# play.net
KiCad netlist of a schematic drawn in EAGLE
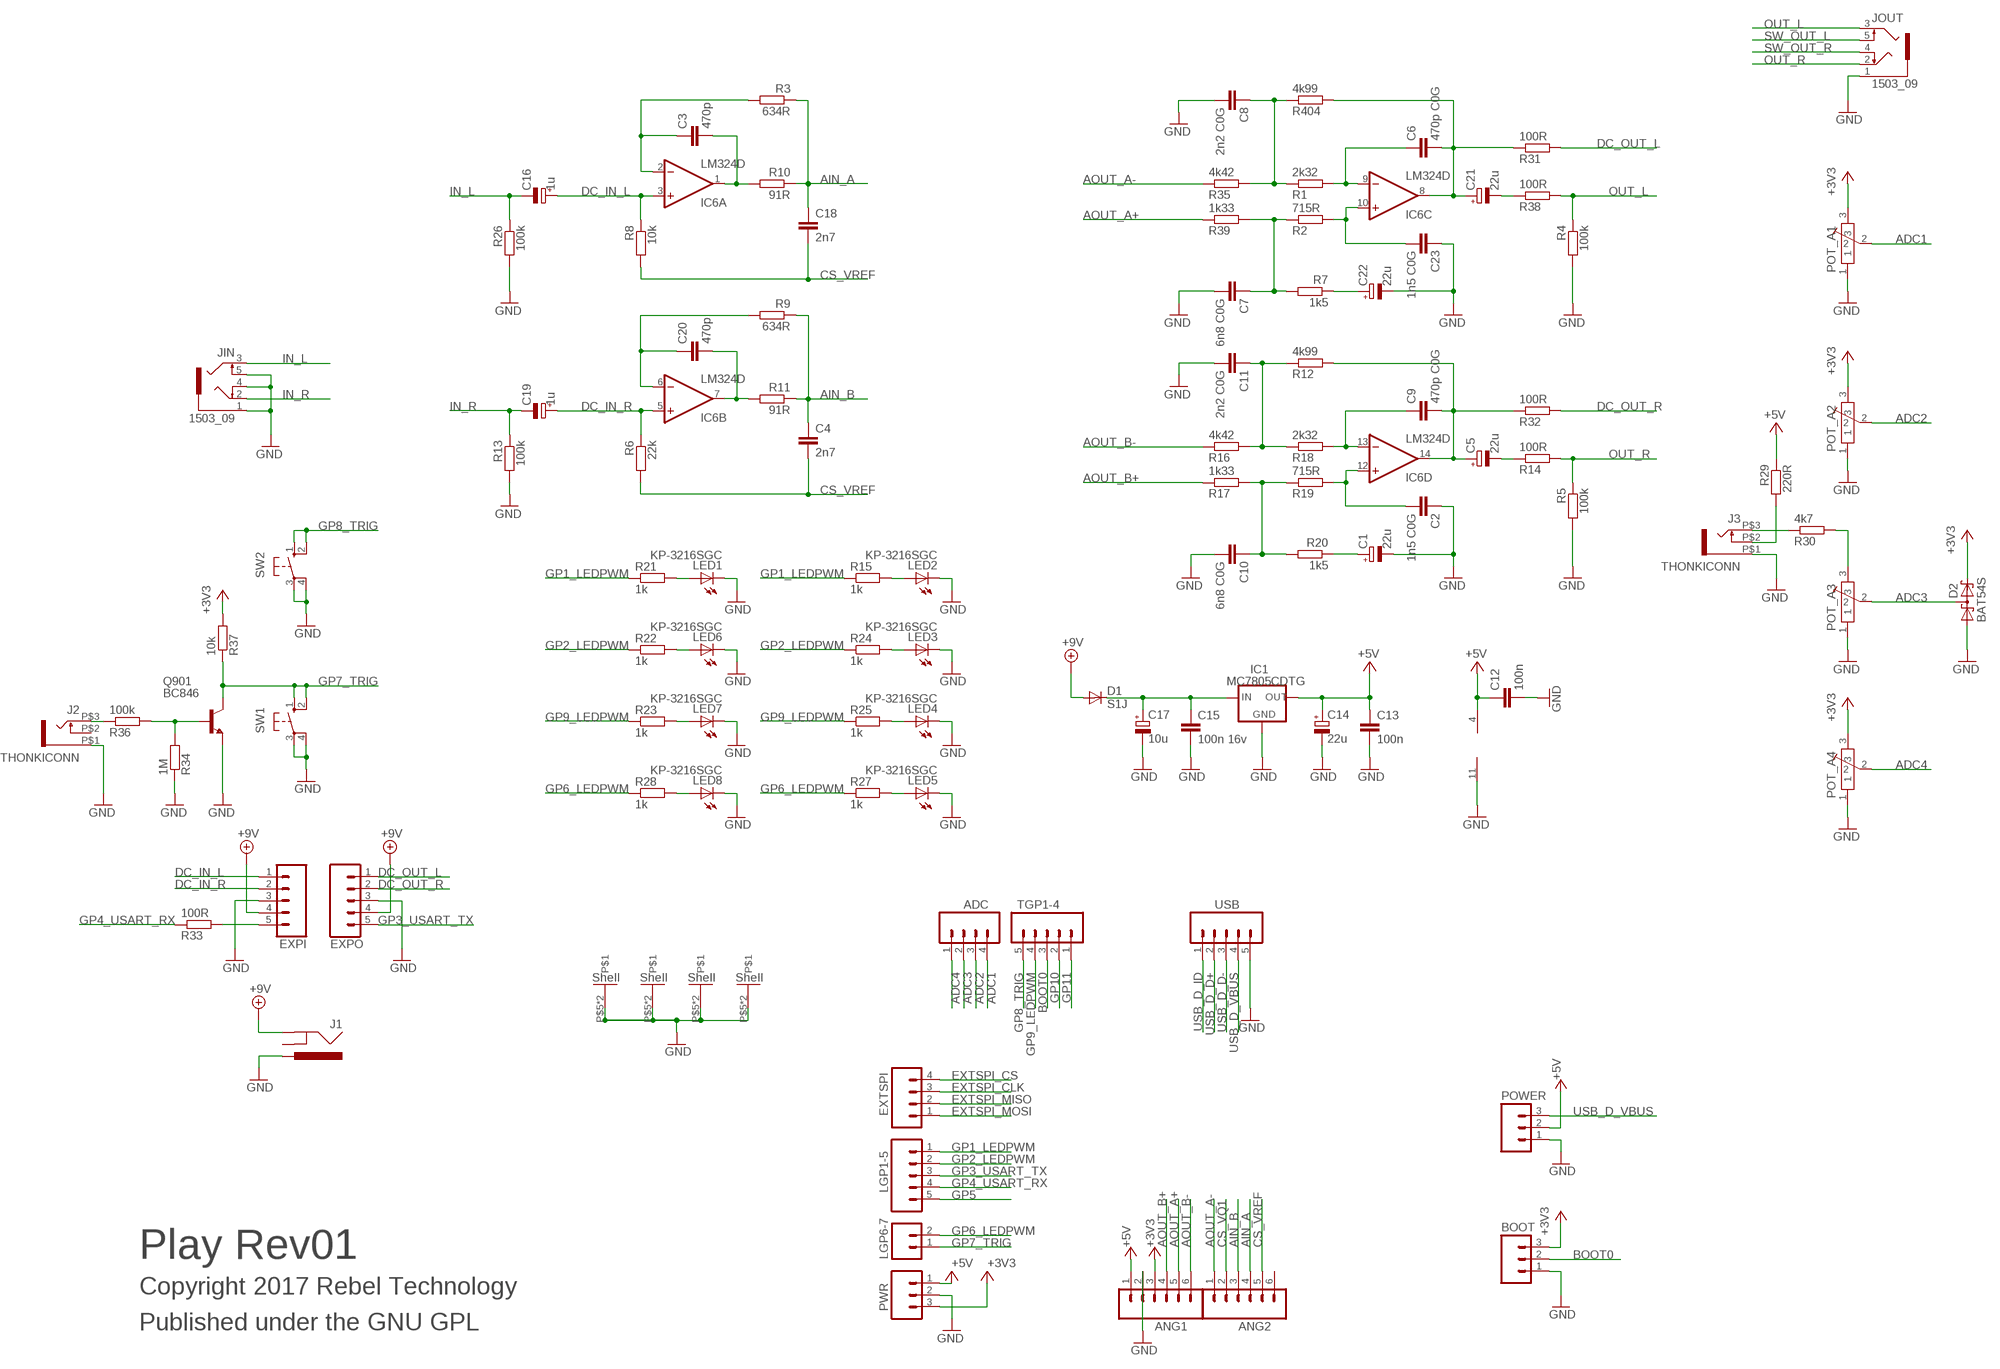
[diagram p0: schematic, sheet 1]

(export (version "E")
  (design (tool "Eeschema 10.0.6"))
  (components
    (comp (ref "ADC")
      (value "M04PTH")
      (footprint "eagle-import:1X04")
      (libsource (lib "eagle-import") (part "M04PTH"))
    )
    (comp (ref "ANG1")
      (value "M06SIP")
      (footprint "eagle-import:1X06")
      (libsource (lib "eagle-import") (part "M06SIP"))
    )
    (comp (ref "ANG2")
      (value "M06SIP")
      (footprint "eagle-import:1X06")
      (libsource (lib "eagle-import") (part "M06SIP"))
    )
    (comp (ref "BOOT")
      (value "M03PTH")
      (footprint "eagle-import:1X03")
      (libsource (lib "eagle-import") (part "M03PTH"))
    )
    (comp (ref "C1")
      (value "22u")
      (footprint "eagle-import:CPOL-5")
      (libsource (lib "eagle-import") (part "CPOL-EU153CLV-0505"))
    )
    (comp (ref "C2")
      (value "1n5 C0G")
      (footprint "eagle-import:C0603")
      (libsource (lib "eagle-import") (part "resistor_C-EUC0603"))
    )
    (comp (ref "C3")
      (value "470p")
      (footprint "eagle-import:C0603")
      (libsource (lib "eagle-import") (part "resistor_C-EUC0603"))
    )
    (comp (ref "C4")
      (value "2n7")
      (footprint "eagle-import:C0603")
      (libsource (lib "eagle-import") (part "resistor_C-EUC0603"))
    )
    (comp (ref "C5")
      (value "22u")
      (footprint "eagle-import:CPOL-5")
      (libsource (lib "eagle-import") (part "CPOL-EU153CLV-0505"))
    )
    (comp (ref "C6")
      (value "470p C0G")
      (footprint "eagle-import:C0603")
      (libsource (lib "eagle-import") (part "resistor_C-EUC0603"))
    )
    (comp (ref "C7")
      (value "6n8 C0G")
      (footprint "eagle-import:C0603")
      (libsource (lib "eagle-import") (part "resistor_C-EUC0603"))
    )
    (comp (ref "C8")
      (value "2n2 C0G")
      (footprint "eagle-import:C0603")
      (libsource (lib "eagle-import") (part "resistor_C-EUC0603"))
    )
    (comp (ref "C9")
      (value "470p C0G")
      (footprint "eagle-import:C0603")
      (libsource (lib "eagle-import") (part "resistor_C-EUC0603"))
    )
    (comp (ref "C10")
      (value "6n8 C0G")
      (footprint "eagle-import:C0603")
      (libsource (lib "eagle-import") (part "resistor_C-EUC0603"))
    )
    (comp (ref "C11")
      (value "2n2 C0G")
      (footprint "eagle-import:C0603")
      (libsource (lib "eagle-import") (part "resistor_C-EUC0603"))
    )
    (comp (ref "C12")
      (value "100n")
      (footprint "eagle-import:C0603")
      (libsource (lib "eagle-import") (part "resistor_C-EUC0603"))
    )
    (comp (ref "C13")
      (value "100n")
      (footprint "eagle-import:C0603")
      (libsource (lib "eagle-import") (part "C-EUC0603"))
    )
    (comp (ref "C14")
      (value "22u")
      (footprint "eagle-import:CPOL-5")
      (libsource (lib "eagle-import") (part "CPOL-EU153CLV-0505"))
    )
    (comp (ref "C15")
      (value "100n 16v")
      (footprint "eagle-import:C0603")
      (libsource (lib "eagle-import") (part "C-EUC0603"))
    )
    (comp (ref "C16")
      (value "1u")
      (footprint "eagle-import:153CLV-0405")
      (libsource (lib "eagle-import") (part "CPOL-EU153CLV-0405"))
    )
    (comp (ref "C17")
      (value "10u")
      (footprint "eagle-import:153CLV-0405")
      (libsource (lib "eagle-import") (part "CPOL-EU153CLV-0405"))
    )
    (comp (ref "C18")
      (value "2n7")
      (footprint "eagle-import:C0603")
      (libsource (lib "eagle-import") (part "resistor_C-EUC0603"))
    )
    (comp (ref "C19")
      (value "1u")
      (footprint "eagle-import:153CLV-0405")
      (libsource (lib "eagle-import") (part "CPOL-EU153CLV-0405"))
    )
    (comp (ref "C20")
      (value "470p")
      (footprint "eagle-import:C0603")
      (libsource (lib "eagle-import") (part "resistor_C-EUC0603"))
    )
    (comp (ref "C21")
      (value "22u")
      (footprint "eagle-import:CPOL-5")
      (libsource (lib "eagle-import") (part "CPOL-EU153CLV-0505"))
    )
    (comp (ref "C22")
      (value "22u")
      (footprint "eagle-import:CPOL-5")
      (libsource (lib "eagle-import") (part "CPOL-EU153CLV-0505"))
    )
    (comp (ref "C23")
      (value "1n5 C0G")
      (footprint "eagle-import:C0603")
      (libsource (lib "eagle-import") (part "resistor_C-EUC0603"))
    )
    (comp (ref "D1")
      (value "S1J")
      (footprint "eagle-import:SMA-DIODE")
      (libsource (lib "eagle-import") (part "DIODESMA"))
    )
    (comp (ref "D2")
      (value "BAT54S")
      (footprint "eagle-import:SOT23")
      (libsource (lib "eagle-import") (part "BAT54S"))
    )
    (comp (ref "EXPI")
      (value "M05PTH")
      (footprint "eagle-import:1X05")
      (libsource (lib "eagle-import") (part "M05PTH"))
    )
    (comp (ref "EXPO")
      (value "M05PTH")
      (footprint "eagle-import:1X05")
      (libsource (lib "eagle-import") (part "M05PTH"))
    )
    (comp (ref "EXTSPI")
      (value "M04PTH")
      (footprint "eagle-import:1X04")
      (libsource (lib "eagle-import") (part "M04PTH"))
    )
    (comp (ref "IC1")
      (value "MC7805CDTG")
      (footprint "eagle-import:DPACK")
      (libsource (lib "eagle-import") (part "MC78XX"))
    )
    (comp (ref "IC6")
      (value "LM324D")
      (footprint "eagle-import:SO14")
      (libsource (lib "eagle-import") (part "LM324D"))
    )
    (comp (ref "J1")
      (value "POWER_JACKPTH")
      (footprint "eagle-import:POWER_JACK_PTH")
      (libsource (lib "eagle-import") (part "POWER_JACKPTH"))
    )
    (comp (ref "J2")
      (value "THONKICONN")
      (footprint "eagle-import:THONKICONN")
      (libsource (lib "eagle-import") (part "THONKICONN"))
    )
    (comp (ref "J3")
      (value "THONKICONN")
      (footprint "eagle-import:THONKICONN")
      (libsource (lib "eagle-import") (part "THONKICONN"))
    )
    (comp (ref "JIN")
      (value "1503_09")
      (footprint "eagle-import:1503_09")
      (libsource (lib "eagle-import") (part "1503_09"))
    )
    (comp (ref "JOUT")
      (value "1503_09")
      (footprint "eagle-import:1503_09")
      (libsource (lib "eagle-import") (part "1503_09"))
    )
    (comp (ref "LED1")
      (value "KP-3216SGC")
      (footprint "eagle-import:LED-1206")
      (libsource (lib "eagle-import") (part "LED1206"))
    )
    (comp (ref "LED2")
      (value "KP-3216SGC")
      (footprint "eagle-import:LED-1206")
      (libsource (lib "eagle-import") (part "LED1206"))
    )
    (comp (ref "LED3")
      (value "KP-3216SGC")
      (footprint "eagle-import:LED-1206")
      (libsource (lib "eagle-import") (part "LED1206"))
    )
    (comp (ref "LED4")
      (value "KP-3216SGC")
      (footprint "eagle-import:LED-1206")
      (libsource (lib "eagle-import") (part "LED1206"))
    )
    (comp (ref "LED5")
      (value "KP-3216SGC")
      (footprint "eagle-import:LED-1206")
      (libsource (lib "eagle-import") (part "LED1206"))
    )
    (comp (ref "LED6")
      (value "KP-3216SGC")
      (footprint "eagle-import:LED-1206")
      (libsource (lib "eagle-import") (part "LED1206"))
    )
    (comp (ref "LED7")
      (value "KP-3216SGC")
      (footprint "eagle-import:LED-1206")
      (libsource (lib "eagle-import") (part "LED1206"))
    )
    (comp (ref "LED8")
      (value "KP-3216SGC")
      (footprint "eagle-import:LED-1206")
      (libsource (lib "eagle-import") (part "LED1206"))
    )
    (comp (ref "LGP1-5")
      (value "M05PTH")
      (footprint "eagle-import:1X05")
      (libsource (lib "eagle-import") (part "M05PTH"))
    )
    (comp (ref "LGP6-7")
      (value "M02PTH")
      (footprint "eagle-import:1X02")
      (libsource (lib "eagle-import") (part "M02PTH"))
    )
    (comp (ref "POT_A1")
      (value "POT-ALPS-RK09L1140")
      (footprint "eagle-import:POT-ALPS-RK09L1140")
      (libsource (lib "eagle-import") (part "POT-ALPS-RK09L1140"))
    )
    (comp (ref "POT_A2")
      (value "POT-ALPS-RK09L1140")
      (footprint "eagle-import:POT-ALPS-RK09L1140")
      (libsource (lib "eagle-import") (part "POT-ALPS-RK09L1140"))
    )
    (comp (ref "POT_A3")
      (value "POT-ALPS-RK09L1140")
      (footprint "eagle-import:POT-ALPS-RK09L1140")
      (libsource (lib "eagle-import") (part "POT-ALPS-RK09L1140"))
    )
    (comp (ref "POT_A4")
      (value "POT-ALPS-RK09L1140")
      (footprint "eagle-import:POT-ALPS-RK09L1140")
      (libsource (lib "eagle-import") (part "POT-ALPS-RK09L1140"))
    )
    (comp (ref "POWER")
      (value "M03PTH")
      (footprint "eagle-import:1X03")
      (libsource (lib "eagle-import") (part "M03PTH"))
    )
    (comp (ref "PWR")
      (value "M03PTH")
      (footprint "eagle-import:1X03")
      (libsource (lib "eagle-import") (part "M03PTH"))
    )
    (comp (ref "Q901")
      (value "BC846")
      (footprint "eagle-import:SOT23")
      (libsource (lib "eagle-import") (part "BC846"))
    )
    (comp (ref "R1")
      (value "2k32")
      (footprint "eagle-import:0603")
      (libsource (lib "eagle-import") (part "R-EU_0603"))
    )
    (comp (ref "R2")
      (value "715R")
      (footprint "eagle-import:0603")
      (libsource (lib "eagle-import") (part "R-EU_0603"))
    )
    (comp (ref "R3")
      (value "634R")
      (footprint "eagle-import:0603")
      (libsource (lib "eagle-import") (part "R-EU_0603"))
    )
    (comp (ref "R4")
      (value "100k")
      (footprint "eagle-import:0603")
      (libsource (lib "eagle-import") (part "R-EU_0603"))
    )
    (comp (ref "R5")
      (value "100k")
      (footprint "eagle-import:0603")
      (libsource (lib "eagle-import") (part "R-EU_0603"))
    )
    (comp (ref "R6")
      (value "22k")
      (footprint "eagle-import:0603")
      (libsource (lib "eagle-import") (part "R-EU_0603"))
    )
    (comp (ref "R7")
      (value "1k5")
      (footprint "eagle-import:0603")
      (libsource (lib "eagle-import") (part "R-EU_0603"))
    )
    (comp (ref "R8")
      (value "10k")
      (footprint "eagle-import:0603")
      (libsource (lib "eagle-import") (part "R-EU_0603"))
    )
    (comp (ref "R9")
      (value "634R")
      (footprint "eagle-import:0603")
      (libsource (lib "eagle-import") (part "R-EU_0603"))
    )
    (comp (ref "R10")
      (value "91R")
      (footprint "eagle-import:0603")
      (libsource (lib "eagle-import") (part "R-EU_0603"))
    )
    (comp (ref "R11")
      (value "91R")
      (footprint "eagle-import:0603")
      (libsource (lib "eagle-import") (part "R-EU_0603"))
    )
    (comp (ref "R12")
      (value "4k99")
      (footprint "eagle-import:0603")
      (libsource (lib "eagle-import") (part "R-EU_0603"))
    )
    (comp (ref "R13")
      (value "100k")
      (footprint "eagle-import:0603")
      (libsource (lib "eagle-import") (part "R-EU_0603"))
    )
    (comp (ref "R14")
      (value "100R")
      (footprint "eagle-import:0603")
      (libsource (lib "eagle-import") (part "R-EU_0603"))
    )
    (comp (ref "R15")
      (value "1k")
      (footprint "eagle-import:0603")
      (libsource (lib "eagle-import") (part "R-EU_0603"))
    )
    (comp (ref "R16")
      (value "4k42")
      (footprint "eagle-import:0603")
      (libsource (lib "eagle-import") (part "R-EU_0603"))
    )
    (comp (ref "R17")
      (value "1k33")
      (footprint "eagle-import:0603")
      (libsource (lib "eagle-import") (part "R-EU_0603"))
    )
    (comp (ref "R18")
      (value "2k32")
      (footprint "eagle-import:0603")
      (libsource (lib "eagle-import") (part "R-EU_0603"))
    )
    (comp (ref "R19")
      (value "715R")
      (footprint "eagle-import:0603")
      (libsource (lib "eagle-import") (part "R-EU_0603"))
    )
    (comp (ref "R20")
      (value "1k5")
      (footprint "eagle-import:0603")
      (libsource (lib "eagle-import") (part "R-EU_0603"))
    )
    (comp (ref "R21")
      (value "1k")
      (footprint "eagle-import:0603")
      (libsource (lib "eagle-import") (part "R-EU_0603"))
    )
    (comp (ref "R22")
      (value "1k")
      (footprint "eagle-import:0603")
      (libsource (lib "eagle-import") (part "R-EU_0603"))
    )
    (comp (ref "R23")
      (value "1k")
      (footprint "eagle-import:0603")
      (libsource (lib "eagle-import") (part "R-EU_0603"))
    )
    (comp (ref "R24")
      (value "1k")
      (footprint "eagle-import:0603")
      (libsource (lib "eagle-import") (part "R-EU_0603"))
    )
    (comp (ref "R25")
      (value "1k")
      (footprint "eagle-import:0603")
      (libsource (lib "eagle-import") (part "R-EU_0603"))
    )
    (comp (ref "R26")
      (value "100k")
      (footprint "eagle-import:0603")
      (libsource (lib "eagle-import") (part "R-EU_0603"))
    )
    (comp (ref "R27")
      (value "1k")
      (footprint "eagle-import:0603")
      (libsource (lib "eagle-import") (part "R-EU_0603"))
    )
    (comp (ref "R28")
      (value "1k")
      (footprint "eagle-import:0603")
      (libsource (lib "eagle-import") (part "R-EU_0603"))
    )
    (comp (ref "R29")
      (value "220R")
      (footprint "eagle-import:0603")
      (libsource (lib "eagle-import") (part "R-EU_0603"))
    )
    (comp (ref "R30")
      (value "4k7")
      (footprint "eagle-import:0603")
      (libsource (lib "eagle-import") (part "R-EU_0603"))
    )
    (comp (ref "R31")
      (value "100R")
      (footprint "eagle-import:0603")
      (libsource (lib "eagle-import") (part "R-EU_0603"))
    )
    (comp (ref "R32")
      (value "100R")
      (footprint "eagle-import:0603")
      (libsource (lib "eagle-import") (part "R-EU_0603"))
    )
    (comp (ref "R33")
      (value "100R")
      (footprint "eagle-import:0603")
      (libsource (lib "eagle-import") (part "R-EU_0603"))
    )
    (comp (ref "R34")
      (value "1M")
      (footprint "eagle-import:0603")
      (libsource (lib "eagle-import") (part "R-EU_0603"))
    )
    (comp (ref "R35")
      (value "4k42")
      (footprint "eagle-import:0603")
      (libsource (lib "eagle-import") (part "R-EU_0603"))
    )
    (comp (ref "R36")
      (value "100k")
      (footprint "eagle-import:0603")
      (libsource (lib "eagle-import") (part "R-EU_0603"))
    )
    (comp (ref "R37")
      (value "10k")
      (footprint "eagle-import:0603")
      (libsource (lib "eagle-import") (part "R-EU_0603"))
    )
    (comp (ref "R38")
      (value "100R")
      (footprint "eagle-import:0603")
      (libsource (lib "eagle-import") (part "R-EU_0603"))
    )
    (comp (ref "R39")
      (value "1k33")
      (footprint "eagle-import:0603")
      (libsource (lib "eagle-import") (part "R-EU_0603"))
    )
    (comp (ref "R404")
      (value "4k99")
      (footprint "eagle-import:0603")
      (libsource (lib "eagle-import") (part "R-EU_0603"))
    )
    (comp (ref "SW1")
      (value "10-XX")
      (footprint "eagle-import:B3F-10XX")
      (fields (field (name "MPN") "B3F-1000"))
      (libsource (lib "eagle-import") (part "10-XX"))
    )
    (comp (ref "SW2")
      (value "10-XX")
      (footprint "eagle-import:B3F-10XX")
      (fields (field (name "MPN") "B3F-1000"))
      (libsource (lib "eagle-import") (part "10-XX"))
    )
    (comp (ref "TGP1-4")
      (value "M05PTH")
      (footprint "eagle-import:1X05")
      (libsource (lib "eagle-import") (part "M05PTH"))
    )
    (comp (ref "USB")
      (value "M05PTH")
      (footprint "eagle-import:1X05")
      (libsource (lib "eagle-import") (part "M05PTH"))
    )
  )
  (nets
    (net (code "1") (name "+3V3") (class "Default")
      (node (ref "ANG1") (pin "3") (pinfunction "3_3") (pintype "passive"))
      (node (ref "BOOT") (pin "3") (pinfunction "3_3") (pintype "passive"))
      (node (ref "D2") (pin "2") (pinfunction "C2_2") (pintype "passive"))
      (node (ref "POT_A1") (pin "3") (pinfunction "3_3") (pintype "bidirectional"))
      (node (ref "POT_A2") (pin "3") (pinfunction "3_3") (pintype "bidirectional"))
      (node (ref "POT_A4") (pin "3") (pinfunction "3_3") (pintype "bidirectional"))
      (node (ref "PWR") (pin "3") (pinfunction "3_3") (pintype "passive"))
      (node (ref "R37") (pin "2") (pinfunction "2_2") (pintype "passive"))
    )
    (net (code "2") (name "+5V") (class "Default")
      (node (ref "ANG1") (pin "1") (pinfunction "1_1") (pintype "passive"))
      (node (ref "C12") (pin "1") (pinfunction "1_1") (pintype "passive"))
      (node (ref "C13") (pin "1") (pinfunction "1_1") (pintype "passive"))
      (node (ref "C14") (pin "+") (pinfunction "+_+") (pintype "passive"))
      (node (ref "IC1") (pin "3") (pinfunction "OUT_3") (pintype "passive"))
      (node (ref "IC6") (pin "4") (pinfunction "V+_4") (pintype "power_in"))
      (node (ref "POWER") (pin "2") (pinfunction "2_2") (pintype "passive"))
      (node (ref "PWR") (pin "1") (pinfunction "1_1") (pintype "passive"))
      (node (ref "R29") (pin "1") (pinfunction "1_1") (pintype "passive"))
    )
    (net (code "3") (name "+9V") (class "Default")
      (node (ref "D1") (pin "A") (pinfunction "A_A") (pintype "passive"))
      (node (ref "EXPI") (pin "4") (pinfunction "4_4") (pintype "passive"))
      (node (ref "EXPO") (pin "4") (pinfunction "4_4") (pintype "passive"))
      (node (ref "J1") (pin "GND") (pinfunction "GND_GND") (pintype "bidirectional"))
    )
    (net (code "4") (name "/ADC1") (class "Default")
      (node (ref "ADC") (pin "4") (pinfunction "4_4") (pintype "passive"))
      (node (ref "POT_A1") (pin "2") (pinfunction "2_2") (pintype "bidirectional"))
    )
    (net (code "5") (name "/ADC2") (class "Default")
      (node (ref "ADC") (pin "3") (pinfunction "3_3") (pintype "passive"))
      (node (ref "POT_A2") (pin "2") (pinfunction "2_2") (pintype "bidirectional"))
    )
    (net (code "6") (name "/ADC3") (class "Default")
      (node (ref "ADC") (pin "2") (pinfunction "2_2") (pintype "passive"))
      (node (ref "D2") (pin "3") (pinfunction "C1A2_3") (pintype "passive"))
      (node (ref "POT_A3") (pin "2") (pinfunction "2_2") (pintype "bidirectional"))
    )
    (net (code "7") (name "/ADC4") (class "Default")
      (node (ref "ADC") (pin "1") (pinfunction "1_1") (pintype "passive"))
      (node (ref "POT_A4") (pin "2") (pinfunction "2_2") (pintype "bidirectional"))
    )
    (net (code "8") (name "/AIN_A") (class "Default")
      (node (ref "ANG2") (pin "4") (pinfunction "4_4") (pintype "passive"))
      (node (ref "C18") (pin "1") (pinfunction "1_1") (pintype "passive"))
      (node (ref "R10") (pin "1") (pinfunction "1_1") (pintype "passive"))
      (node (ref "R3") (pin "1") (pinfunction "1_1") (pintype "passive"))
    )
    (net (code "9") (name "/AIN_B") (class "Default")
      (node (ref "ANG2") (pin "3") (pinfunction "3_3") (pintype "passive"))
      (node (ref "C4") (pin "1") (pinfunction "1_1") (pintype "passive"))
      (node (ref "R11") (pin "1") (pinfunction "1_1") (pintype "passive"))
      (node (ref "R9") (pin "1") (pinfunction "1_1") (pintype "passive"))
    )
    (net (code "10") (name "/AOUT_A+") (class "Default")
      (node (ref "ANG1") (pin "5") (pinfunction "5_5") (pintype "passive"))
      (node (ref "R39") (pin "1") (pinfunction "1_1") (pintype "passive"))
    )
    (net (code "11") (name "/AOUT_A-") (class "Default")
      (node (ref "ANG2") (pin "1") (pinfunction "1_1") (pintype "passive"))
      (node (ref "R35") (pin "1") (pinfunction "1_1") (pintype "passive"))
    )
    (net (code "12") (name "/AOUT_B+") (class "Default")
      (node (ref "ANG1") (pin "4") (pinfunction "4_4") (pintype "passive"))
      (node (ref "R17") (pin "1") (pinfunction "1_1") (pintype "passive"))
    )
    (net (code "13") (name "/AOUT_B-") (class "Default")
      (node (ref "ANG1") (pin "6") (pinfunction "6_6") (pintype "passive"))
      (node (ref "R16") (pin "1") (pinfunction "1_1") (pintype "passive"))
    )
    (net (code "14") (name "/BOOT0") (class "Default")
      (node (ref "BOOT") (pin "2") (pinfunction "2_2") (pintype "passive"))
      (node (ref "TGP1-4") (pin "3") (pinfunction "3_3") (pintype "passive"))
    )
    (net (code "15") (name "/CS_VQ1") (class "Default")
      (node (ref "ANG2") (pin "2") (pinfunction "2_2") (pintype "passive"))
    )
    (net (code "16") (name "/CS_VREF") (class "Default")
      (node (ref "ANG2") (pin "5") (pinfunction "5_5") (pintype "passive"))
      (node (ref "C18") (pin "2") (pinfunction "2_2") (pintype "passive"))
      (node (ref "C4") (pin "2") (pinfunction "2_2") (pintype "passive"))
      (node (ref "R6") (pin "2") (pinfunction "2_2") (pintype "passive"))
      (node (ref "R8") (pin "2") (pinfunction "2_2") (pintype "passive"))
    )
    (net (code "17") (name "/DC_IN_L") (class "Default")
      (node (ref "C16") (pin "+") (pinfunction "+_+") (pintype "passive"))
      (node (ref "EXPI") (pin "1") (pinfunction "1_1") (pintype "passive"))
      (node (ref "IC6") (pin "3") (pinfunction "+IN_3") (pintype "input"))
      (node (ref "R8") (pin "1") (pinfunction "1_1") (pintype "passive"))
    )
    (net (code "18") (name "/DC_IN_R") (class "Default")
      (node (ref "C19") (pin "+") (pinfunction "+_+") (pintype "passive"))
      (node (ref "EXPI") (pin "2") (pinfunction "2_2") (pintype "passive"))
      (node (ref "IC6") (pin "5") (pinfunction "+IN_5") (pintype "input"))
      (node (ref "R6") (pin "1") (pinfunction "1_1") (pintype "passive"))
    )
    (net (code "19") (name "/DC_OUT_L") (class "Default")
      (node (ref "EXPO") (pin "1") (pinfunction "1_1") (pintype "passive"))
      (node (ref "R31") (pin "2") (pinfunction "2_2") (pintype "passive"))
    )
    (net (code "20") (name "/DC_OUT_R") (class "Default")
      (node (ref "EXPO") (pin "2") (pinfunction "2_2") (pintype "passive"))
      (node (ref "R32") (pin "2") (pinfunction "2_2") (pintype "passive"))
    )
    (net (code "21") (name "/EXTSPI_CLK") (class "Default")
      (node (ref "EXTSPI") (pin "3") (pinfunction "3_3") (pintype "passive"))
    )
    (net (code "22") (name "/EXTSPI_CS") (class "Default")
      (node (ref "EXTSPI") (pin "4") (pinfunction "4_4") (pintype "passive"))
    )
    (net (code "23") (name "/EXTSPI_MISO") (class "Default")
      (node (ref "EXTSPI") (pin "2") (pinfunction "2_2") (pintype "passive"))
    )
    (net (code "24") (name "/EXTSPI_MOSI") (class "Default")
      (node (ref "EXTSPI") (pin "1") (pinfunction "1_1") (pintype "passive"))
    )
    (net (code "25") (name "/GP1_LEDPWM") (class "Default")
      (node (ref "LGP1-5") (pin "1") (pinfunction "1_1") (pintype "passive"))
      (node (ref "R15") (pin "1") (pinfunction "1_1") (pintype "passive"))
      (node (ref "R21") (pin "1") (pinfunction "1_1") (pintype "passive"))
    )
    (net (code "26") (name "/GP2_LEDPWM") (class "Default")
      (node (ref "LGP1-5") (pin "2") (pinfunction "2_2") (pintype "passive"))
      (node (ref "R22") (pin "1") (pinfunction "1_1") (pintype "passive"))
      (node (ref "R24") (pin "1") (pinfunction "1_1") (pintype "passive"))
    )
    (net (code "27") (name "/GP3_USART_TX") (class "Default")
      (node (ref "EXPO") (pin "5") (pinfunction "5_5") (pintype "passive"))
      (node (ref "LGP1-5") (pin "3") (pinfunction "3_3") (pintype "passive"))
    )
    (net (code "28") (name "/GP4_USART_RX") (class "Default")
      (node (ref "LGP1-5") (pin "4") (pinfunction "4_4") (pintype "passive"))
      (node (ref "R33") (pin "1") (pinfunction "1_1") (pintype "passive"))
    )
    (net (code "29") (name "/GP5") (class "Default")
      (node (ref "LGP1-5") (pin "5") (pinfunction "5_5") (pintype "passive"))
    )
    (net (code "30") (name "/GP6_LEDPWM") (class "Default")
      (node (ref "LGP6-7") (pin "2") (pinfunction "2_2") (pintype "passive"))
      (node (ref "R27") (pin "1") (pinfunction "1_1") (pintype "passive"))
      (node (ref "R28") (pin "1") (pinfunction "1_1") (pintype "passive"))
    )
    (net (code "31") (name "/GP7_TRIG") (class "Default")
      (node (ref "LGP6-7") (pin "1") (pinfunction "1_1") (pintype "passive"))
      (node (ref "Q901") (pin "3") (pinfunction "C_3") (pintype "passive"))
      (node (ref "R37") (pin "1") (pinfunction "1_1") (pintype "passive"))
      (node (ref "SW1") (pin "1") (pinfunction "S_1") (pintype "passive"))
      (node (ref "SW1") (pin "2") (pinfunction "S1_2") (pintype "passive"))
    )
    (net (code "32") (name "/GP8_TRIG") (class "Default")
      (node (ref "SW2") (pin "1") (pinfunction "S_1") (pintype "passive"))
      (node (ref "SW2") (pin "2") (pinfunction "S1_2") (pintype "passive"))
      (node (ref "TGP1-4") (pin "5") (pinfunction "5_5") (pintype "passive"))
    )
    (net (code "33") (name "/GP9_LEDPWM") (class "Default")
      (node (ref "R23") (pin "1") (pinfunction "1_1") (pintype "passive"))
      (node (ref "R25") (pin "1") (pinfunction "1_1") (pintype "passive"))
      (node (ref "TGP1-4") (pin "4") (pinfunction "4_4") (pintype "passive"))
    )
    (net (code "34") (name "/GP10") (class "Default")
      (node (ref "TGP1-4") (pin "2") (pinfunction "2_2") (pintype "passive"))
    )
    (net (code "35") (name "/GP11") (class "Default")
      (node (ref "TGP1-4") (pin "1") (pinfunction "1_1") (pintype "passive"))
    )
    (net (code "36") (name "/IN_L") (class "Default")
      (node (ref "C16") (pin "-") (pinfunction "-_-") (pintype "passive"))
      (node (ref "JIN") (pin "3") (pinfunction "3_3") (pintype "passive"))
      (node (ref "R26") (pin "1") (pinfunction "1_1") (pintype "passive"))
    )
    (net (code "37") (name "/IN_R") (class "Default")
      (node (ref "C19") (pin "-") (pinfunction "-_-") (pintype "passive"))
      (node (ref "JIN") (pin "2") (pinfunction "2_2") (pintype "passive"))
      (node (ref "R13") (pin "1") (pinfunction "1_1") (pintype "passive"))
    )
    (net (code "38") (name "/OUT_L") (class "Default")
      (node (ref "JOUT") (pin "3") (pinfunction "3_3") (pintype "passive"))
      (node (ref "R38") (pin "2") (pinfunction "2_2") (pintype "passive"))
      (node (ref "R4") (pin "1") (pinfunction "1_1") (pintype "passive"))
    )
    (net (code "39") (name "/OUT_R") (class "Default")
      (node (ref "JOUT") (pin "2") (pinfunction "2_2") (pintype "passive"))
      (node (ref "R14") (pin "2") (pinfunction "2_2") (pintype "passive"))
      (node (ref "R5") (pin "1") (pinfunction "1_1") (pintype "passive"))
    )
    (net (code "40") (name "/SW_OUT_L") (class "Default")
      (node (ref "JOUT") (pin "5") (pinfunction "5_5") (pintype "passive"))
    )
    (net (code "41") (name "/SW_OUT_R") (class "Default")
      (node (ref "JOUT") (pin "4") (pinfunction "4_4") (pintype "passive"))
    )
    (net (code "42") (name "/USB_D_D+") (class "Default")
      (node (ref "USB") (pin "2") (pinfunction "2_2") (pintype "passive"))
    )
    (net (code "43") (name "/USB_D_D-") (class "Default")
      (node (ref "USB") (pin "3") (pinfunction "3_3") (pintype "passive"))
    )
    (net (code "44") (name "/USB_D_ID") (class "Default")
      (node (ref "USB") (pin "1") (pinfunction "1_1") (pintype "passive"))
    )
    (net (code "45") (name "/USB_D_VBUS") (class "Default")
      (node (ref "POWER") (pin "3") (pinfunction "3_3") (pintype "passive"))
      (node (ref "USB") (pin "4") (pinfunction "4_4") (pintype "passive"))
    )
    (net (code "46") (name "GND") (class "Default")
      (node (ref "ANG1") (pin "2") (pinfunction "2_2") (pintype "passive"))
      (node (ref "BOOT") (pin "1") (pinfunction "1_1") (pintype "passive"))
      (node (ref "C1") (pin "-") (pinfunction "-_-") (pintype "passive"))
      (node (ref "C10") (pin "2") (pinfunction "2_2") (pintype "passive"))
      (node (ref "C11") (pin "2") (pinfunction "2_2") (pintype "passive"))
      (node (ref "C12") (pin "2") (pinfunction "2_2") (pintype "passive"))
      (node (ref "C13") (pin "2") (pinfunction "2_2") (pintype "passive"))
      (node (ref "C14") (pin "-") (pinfunction "-_-") (pintype "passive"))
      (node (ref "C15") (pin "2") (pinfunction "2_2") (pintype "passive"))
      (node (ref "C17") (pin "-") (pinfunction "-_-") (pintype "passive"))
      (node (ref "C2") (pin "1") (pinfunction "1_1") (pintype "passive"))
      (node (ref "C22") (pin "-") (pinfunction "-_-") (pintype "passive"))
      (node (ref "C23") (pin "1") (pinfunction "1_1") (pintype "passive"))
      (node (ref "C7") (pin "2") (pinfunction "2_2") (pintype "passive"))
      (node (ref "C8") (pin "2") (pinfunction "2_2") (pintype "passive"))
      (node (ref "D2") (pin "1") (pinfunction "A1_1") (pintype "passive"))
      (node (ref "EXPI") (pin "3") (pinfunction "3_3") (pintype "passive"))
      (node (ref "EXPO") (pin "3") (pinfunction "3_3") (pintype "passive"))
      (node (ref "IC1") (pin "4") (pinfunction "GND_4") (pintype "input"))
      (node (ref "IC6") (pin "11") (pinfunction "V-_11") (pintype "power_in"))
      (node (ref "J1") (pin "PWR") (pinfunction "PWR_PWR") (pintype "bidirectional"))
      (node (ref "J2") (pin "P$1") (pinfunction "5_P$1") (pintype "passive"))
      (node (ref "J3") (pin "P$1") (pinfunction "5_P$1") (pintype "passive"))
      (node (ref "JIN") (pin "1") (pinfunction "1_1") (pintype "passive"))
      (node (ref "JIN") (pin "4") (pinfunction "4_4") (pintype "passive"))
      (node (ref "JIN") (pin "5") (pinfunction "5_5") (pintype "passive"))
      (node (ref "JOUT") (pin "1") (pinfunction "1_1") (pintype "passive"))
      (node (ref "LED1") (pin "C") (pinfunction "C_C") (pintype "passive"))
      (node (ref "LED2") (pin "C") (pinfunction "C_C") (pintype "passive"))
      (node (ref "LED3") (pin "C") (pinfunction "C_C") (pintype "passive"))
      (node (ref "LED4") (pin "C") (pinfunction "C_C") (pintype "passive"))
      (node (ref "LED5") (pin "C") (pinfunction "C_C") (pintype "passive"))
      (node (ref "LED6") (pin "C") (pinfunction "C_C") (pintype "passive"))
      (node (ref "LED7") (pin "C") (pinfunction "C_C") (pintype "passive"))
      (node (ref "LED8") (pin "C") (pinfunction "C_C") (pintype "passive"))
      (node (ref "POT_A1") (pin "1") (pinfunction "1_1") (pintype "bidirectional"))
      (node (ref "POT_A1") (pin "P$5") (pinfunction "P$1_P$5") (pintype "bidirectional"))
      (node (ref "POT_A1") (pin "P$6") (pinfunction "P$1_P$6") (pintype "bidirectional"))
      (node (ref "POT_A2") (pin "1") (pinfunction "1_1") (pintype "bidirectional"))
      (node (ref "POT_A2") (pin "P$5") (pinfunction "P$1_P$5") (pintype "bidirectional"))
      (node (ref "POT_A2") (pin "P$6") (pinfunction "P$1_P$6") (pintype "bidirectional"))
      (node (ref "POT_A3") (pin "1") (pinfunction "1_1") (pintype "bidirectional"))
      (node (ref "POT_A3") (pin "P$5") (pinfunction "P$1_P$5") (pintype "bidirectional"))
      (node (ref "POT_A3") (pin "P$6") (pinfunction "P$1_P$6") (pintype "bidirectional"))
      (node (ref "POT_A4") (pin "1") (pinfunction "1_1") (pintype "bidirectional"))
      (node (ref "POT_A4") (pin "P$5") (pinfunction "P$1_P$5") (pintype "bidirectional"))
      (node (ref "POT_A4") (pin "P$6") (pinfunction "P$1_P$6") (pintype "bidirectional"))
      (node (ref "POWER") (pin "1") (pinfunction "1_1") (pintype "passive"))
      (node (ref "PWR") (pin "2") (pinfunction "2_2") (pintype "passive"))
      (node (ref "Q901") (pin "2") (pinfunction "E_2") (pintype "passive"))
      (node (ref "R13") (pin "2") (pinfunction "2_2") (pintype "passive"))
      (node (ref "R26") (pin "2") (pinfunction "2_2") (pintype "passive"))
      (node (ref "R34") (pin "1") (pinfunction "1_1") (pintype "passive"))
      (node (ref "R4") (pin "2") (pinfunction "2_2") (pintype "passive"))
      (node (ref "R5") (pin "2") (pinfunction "2_2") (pintype "passive"))
      (node (ref "SW1") (pin "3") (pinfunction "P_3") (pintype "passive"))
      (node (ref "SW1") (pin "4") (pinfunction "P1_4") (pintype "passive"))
      (node (ref "SW2") (pin "3") (pinfunction "P_3") (pintype "passive"))
      (node (ref "SW2") (pin "4") (pinfunction "P1_4") (pintype "passive"))
      (node (ref "USB") (pin "5") (pinfunction "5_5") (pintype "passive"))
    )
    (net (code "47") (name "Net-(C1-Pad+)") (class "Default")
      (node (ref "C1") (pin "+") (pinfunction "+_+") (pintype "passive"))
      (node (ref "R20") (pin "1") (pinfunction "1_1") (pintype "passive"))
    )
    (net (code "48") (name "Net-(C5-Pad-)") (class "Default")
      (node (ref "C5") (pin "-") (pinfunction "-_-") (pintype "passive"))
      (node (ref "R14") (pin "1") (pinfunction "1_1") (pintype "passive"))
    )
    (net (code "49") (name "Net-(C7-Pad1)") (class "Default")
      (node (ref "C7") (pin "1") (pinfunction "1_1") (pintype "passive"))
      (node (ref "R2") (pin "1") (pinfunction "1_1") (pintype "passive"))
      (node (ref "R39") (pin "2") (pinfunction "2_2") (pintype "passive"))
      (node (ref "R7") (pin "2") (pinfunction "2_2") (pintype "passive"))
    )
    (net (code "50") (name "Net-(C8-Pad1)") (class "Default")
      (node (ref "C8") (pin "1") (pinfunction "1_1") (pintype "passive"))
      (node (ref "R1") (pin "1") (pinfunction "1_1") (pintype "passive"))
      (node (ref "R35") (pin "2") (pinfunction "2_2") (pintype "passive"))
      (node (ref "R404") (pin "1") (pinfunction "1_1") (pintype "passive"))
    )
    (net (code "51") (name "Net-(C10-Pad1)") (class "Default")
      (node (ref "C10") (pin "1") (pinfunction "1_1") (pintype "passive"))
      (node (ref "R17") (pin "2") (pinfunction "2_2") (pintype "passive"))
      (node (ref "R19") (pin "1") (pinfunction "1_1") (pintype "passive"))
      (node (ref "R20") (pin "2") (pinfunction "2_2") (pintype "passive"))
    )
    (net (code "52") (name "Net-(C11-Pad1)") (class "Default")
      (node (ref "C11") (pin "1") (pinfunction "1_1") (pintype "passive"))
      (node (ref "R12") (pin "1") (pinfunction "1_1") (pintype "passive"))
      (node (ref "R16") (pin "2") (pinfunction "2_2") (pintype "passive"))
      (node (ref "R18") (pin "1") (pinfunction "1_1") (pintype "passive"))
    )
    (net (code "53") (name "Net-(C21-Pad-)") (class "Default")
      (node (ref "C21") (pin "-") (pinfunction "-_-") (pintype "passive"))
      (node (ref "R38") (pin "1") (pinfunction "1_1") (pintype "passive"))
    )
    (net (code "54") (name "Net-(C22-Pad+)") (class "Default")
      (node (ref "C22") (pin "+") (pinfunction "+_+") (pintype "passive"))
      (node (ref "R7") (pin "1") (pinfunction "1_1") (pintype "passive"))
    )
    (net (code "55") (name "Net-(EXPI-Pad5)") (class "Default")
      (node (ref "EXPI") (pin "5") (pinfunction "5_5") (pintype "passive"))
      (node (ref "R33") (pin "2") (pinfunction "2_2") (pintype "passive"))
    )
    (net (code "56") (name "Net-(IC1-IN)") (class "Default")
      (node (ref "C15") (pin "1") (pinfunction "1_1") (pintype "passive"))
      (node (ref "C17") (pin "+") (pinfunction "+_+") (pintype "passive"))
      (node (ref "D1") (pin "C") (pinfunction "C_C") (pintype "passive"))
      (node (ref "IC1") (pin "1") (pinfunction "IN_1") (pintype "input"))
    )
    (net (code "57") (name "Net-(IC6A--IN)") (class "Default")
      (node (ref "C3") (pin "1") (pinfunction "1_1") (pintype "passive"))
      (node (ref "IC6") (pin "2") (pinfunction "-IN_2") (pintype "input"))
      (node (ref "R3") (pin "2") (pinfunction "2_2") (pintype "passive"))
    )
    (net (code "58") (name "Net-(IC6A-OUT)") (class "Default")
      (node (ref "C3") (pin "2") (pinfunction "2_2") (pintype "passive"))
      (node (ref "IC6") (pin "1") (pinfunction "OUT_1") (pintype "output"))
      (node (ref "R10") (pin "2") (pinfunction "2_2") (pintype "passive"))
    )
    (net (code "59") (name "Net-(IC6B--IN)") (class "Default")
      (node (ref "C20") (pin "1") (pinfunction "1_1") (pintype "passive"))
      (node (ref "IC6") (pin "6") (pinfunction "-IN_6") (pintype "input"))
      (node (ref "R9") (pin "2") (pinfunction "2_2") (pintype "passive"))
    )
    (net (code "60") (name "Net-(IC6B-OUT)") (class "Default")
      (node (ref "C20") (pin "2") (pinfunction "2_2") (pintype "passive"))
      (node (ref "IC6") (pin "7") (pinfunction "OUT_7") (pintype "output"))
      (node (ref "R11") (pin "2") (pinfunction "2_2") (pintype "passive"))
    )
    (net (code "61") (name "Net-(IC6C-+IN)") (class "Default")
      (node (ref "C23") (pin "2") (pinfunction "2_2") (pintype "passive"))
      (node (ref "IC6") (pin "10") (pinfunction "+IN_10") (pintype "input"))
      (node (ref "R2") (pin "2") (pinfunction "2_2") (pintype "passive"))
    )
    (net (code "62") (name "Net-(IC6C--IN)") (class "Default")
      (node (ref "C6") (pin "1") (pinfunction "1_1") (pintype "passive"))
      (node (ref "IC6") (pin "9") (pinfunction "-IN_9") (pintype "input"))
      (node (ref "R1") (pin "2") (pinfunction "2_2") (pintype "passive"))
    )
    (net (code "63") (name "Net-(IC6C-OUT)") (class "Default")
      (node (ref "C21") (pin "+") (pinfunction "+_+") (pintype "passive"))
      (node (ref "C6") (pin "2") (pinfunction "2_2") (pintype "passive"))
      (node (ref "IC6") (pin "8") (pinfunction "OUT_8") (pintype "output"))
      (node (ref "R31") (pin "1") (pinfunction "1_1") (pintype "passive"))
      (node (ref "R404") (pin "2") (pinfunction "2_2") (pintype "passive"))
    )
    (net (code "64") (name "Net-(IC6D-+IN)") (class "Default")
      (node (ref "C2") (pin "2") (pinfunction "2_2") (pintype "passive"))
      (node (ref "IC6") (pin "12") (pinfunction "+IN_12") (pintype "input"))
      (node (ref "R19") (pin "2") (pinfunction "2_2") (pintype "passive"))
    )
    (net (code "65") (name "Net-(IC6D--IN)") (class "Default")
      (node (ref "C9") (pin "1") (pinfunction "1_1") (pintype "passive"))
      (node (ref "IC6") (pin "13") (pinfunction "-IN_13") (pintype "input"))
      (node (ref "R18") (pin "2") (pinfunction "2_2") (pintype "passive"))
    )
    (net (code "66") (name "Net-(IC6D-OUT)") (class "Default")
      (node (ref "C5") (pin "+") (pinfunction "+_+") (pintype "passive"))
      (node (ref "C9") (pin "2") (pinfunction "2_2") (pintype "passive"))
      (node (ref "IC6") (pin "14") (pinfunction "OUT_14") (pintype "output"))
      (node (ref "R12") (pin "2") (pinfunction "2_2") (pintype "passive"))
      (node (ref "R32") (pin "1") (pinfunction "1_1") (pintype "passive"))
    )
    (net (code "67") (name "Net-(J2-3)") (class "Default")
      (node (ref "J2") (pin "P$3") (pinfunction "3_P$3") (pintype "passive"))
      (node (ref "R36") (pin "1") (pinfunction "1_1") (pintype "passive"))
    )
    (net (code "68") (name "Net-(J3-3)") (class "Default")
      (node (ref "J3") (pin "P$3") (pinfunction "3_P$3") (pintype "passive"))
      (node (ref "R30") (pin "1") (pinfunction "1_1") (pintype "passive"))
    )
    (net (code "69") (name "Net-(J3-4)") (class "Default")
      (node (ref "J3") (pin "P$2") (pinfunction "4_P$2") (pintype "passive"))
      (node (ref "R29") (pin "2") (pinfunction "2_2") (pintype "passive"))
    )
    (net (code "70") (name "Net-(LED1-PadA)") (class "Default")
      (node (ref "LED1") (pin "A") (pinfunction "A_A") (pintype "passive"))
      (node (ref "R21") (pin "2") (pinfunction "2_2") (pintype "passive"))
    )
    (net (code "71") (name "Net-(LED2-PadA)") (class "Default")
      (node (ref "LED2") (pin "A") (pinfunction "A_A") (pintype "passive"))
      (node (ref "R15") (pin "2") (pinfunction "2_2") (pintype "passive"))
    )
    (net (code "72") (name "Net-(LED3-PadA)") (class "Default")
      (node (ref "LED3") (pin "A") (pinfunction "A_A") (pintype "passive"))
      (node (ref "R24") (pin "2") (pinfunction "2_2") (pintype "passive"))
    )
    (net (code "73") (name "Net-(LED4-PadA)") (class "Default")
      (node (ref "LED4") (pin "A") (pinfunction "A_A") (pintype "passive"))
      (node (ref "R25") (pin "2") (pinfunction "2_2") (pintype "passive"))
    )
    (net (code "74") (name "Net-(LED5-PadA)") (class "Default")
      (node (ref "LED5") (pin "A") (pinfunction "A_A") (pintype "passive"))
      (node (ref "R27") (pin "2") (pinfunction "2_2") (pintype "passive"))
    )
    (net (code "75") (name "Net-(LED6-PadA)") (class "Default")
      (node (ref "LED6") (pin "A") (pinfunction "A_A") (pintype "passive"))
      (node (ref "R22") (pin "2") (pinfunction "2_2") (pintype "passive"))
    )
    (net (code "76") (name "Net-(LED7-PadA)") (class "Default")
      (node (ref "LED7") (pin "A") (pinfunction "A_A") (pintype "passive"))
      (node (ref "R23") (pin "2") (pinfunction "2_2") (pintype "passive"))
    )
    (net (code "77") (name "Net-(LED8-PadA)") (class "Default")
      (node (ref "LED8") (pin "A") (pinfunction "A_A") (pintype "passive"))
      (node (ref "R28") (pin "2") (pinfunction "2_2") (pintype "passive"))
    )
    (net (code "78") (name "Net-(POT_A3-Pad3)") (class "Default")
      (node (ref "POT_A3") (pin "3") (pinfunction "3_3") (pintype "bidirectional"))
      (node (ref "R30") (pin "2") (pinfunction "2_2") (pintype "passive"))
    )
    (net (code "79") (name "Net-(Q901-B)") (class "Default")
      (node (ref "Q901") (pin "1") (pinfunction "B_1") (pintype "passive"))
      (node (ref "R34") (pin "2") (pinfunction "2_2") (pintype "passive"))
      (node (ref "R36") (pin "2") (pinfunction "2_2") (pintype "passive"))
    )
    (net (code "80") (name "unconnected-(ANG2-Pad6)") (class "Default")
      (node (ref "ANG2") (pin "6") (pinfunction "6_6") (pintype "passive"))
    )
    (net (code "81") (name "unconnected-(J1-PadGNDBREAK)") (class "Default")
      (node (ref "J1") (pin "GNDBREAK") (pinfunction "GNDBREAK_GNDBREAK") (pintype "bidirectional"))
    )
    (net (code "82") (name "unconnected-(J2-4-PadP$2)") (class "Default")
      (node (ref "J2") (pin "P$2") (pinfunction "4_P$2") (pintype "passive"))
    )
  )
)
